# 32pinromtoflash_-_piggyback.net
KiCad netlist of a schematic drawn in EAGLE
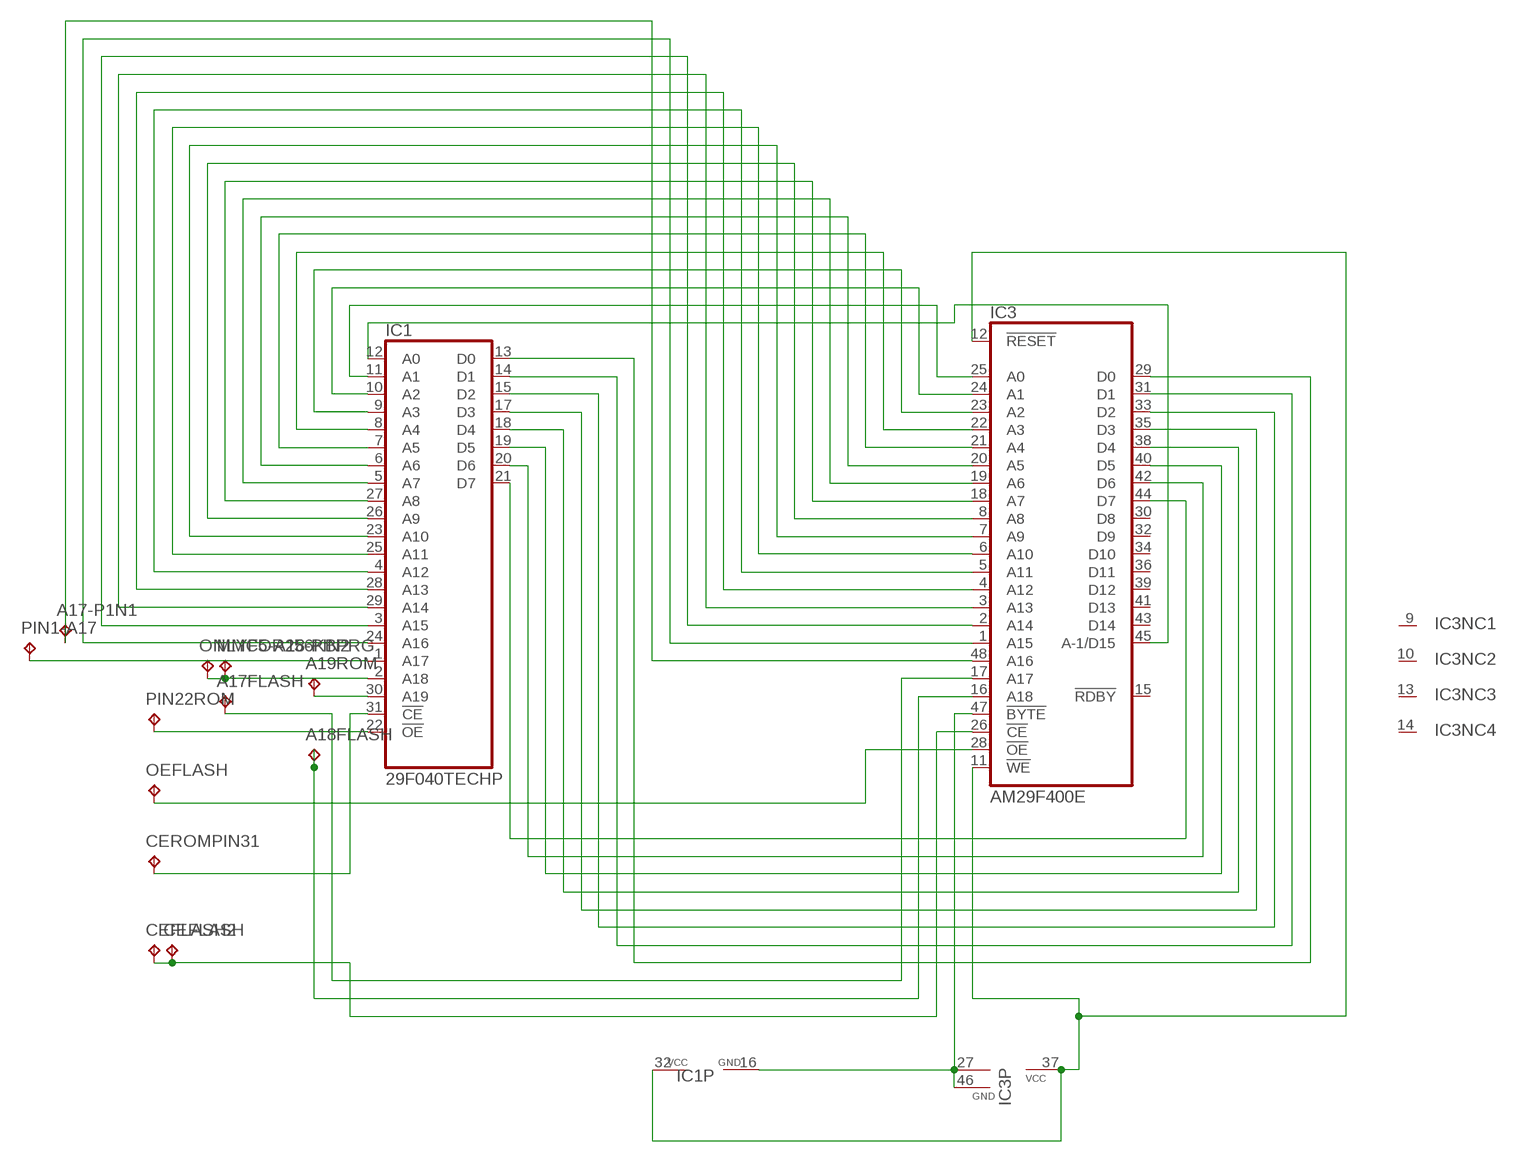
[diagram p0: schematic, sheet 1]

(export (version "E")
  (design (tool "Eeschema 10.0.6"))
  (components
    (comp (ref "A17-P1N1")
      (value "TPTP07SQ")
      (footprint "eagle-import:TP07SQ")
      (libsource (lib "eagle-import") (part "TPTP07SQ"))
    )
    (comp (ref "A17FLASH")
      (value "TPTP07SQ")
      (footprint "eagle-import:TP07SQ")
      (libsource (lib "eagle-import") (part "TPTP07SQ"))
    )
    (comp (ref "A18FLASH")
      (value "TPTP07SQ")
      (footprint "eagle-import:TP07SQ")
      (libsource (lib "eagle-import") (part "TPTP07SQ"))
    )
    (comp (ref "A19ROM")
      (value "TPTP07SQ")
      (footprint "eagle-import:TP07SQ")
      (libsource (lib "eagle-import") (part "TPTP07SQ"))
    )
    (comp (ref "CEFLASH")
      (value "TPTP07SQ")
      (footprint "eagle-import:TP07SQ")
      (libsource (lib "eagle-import") (part "TPTP07SQ"))
    )
    (comp (ref "CEFLASH2")
      (value "TPTP07SQ")
      (footprint "eagle-import:TP07SQ")
      (libsource (lib "eagle-import") (part "TPTP07SQ"))
    )
    (comp (ref "CEROMPIN31")
      (value "TPTP07SQ")
      (footprint "eagle-import:TP07SQ")
      (libsource (lib "eagle-import") (part "TPTP07SQ"))
    )
    (comp (ref "IC1")
      (value "29F040TECHP")
      (footprint "eagle-import:DIL32-3")
      (libsource (lib "eagle-import") (part "29F040PTECH"))
    )
    (comp (ref "IC3")
      (value "AM29F400E")
      (footprint "eagle-import:TSOP48")
      (libsource (lib "eagle-import") (part "AM29F400E"))
    )
    (comp (ref "MMC5-A18-PIN2")
      (value "TPTP07SQ")
      (footprint "eagle-import:TP07SQ")
      (libsource (lib "eagle-import") (part "TPTP07SQ"))
    )
    (comp (ref "OEFLASH")
      (value "TPTP07SQ")
      (footprint "eagle-import:TP07SQ")
      (libsource (lib "eagle-import") (part "TPTP07SQ"))
    )
    (comp (ref "ONLYFOR256KBPRG")
      (value "TPTP07SQ")
      (footprint "eagle-import:TP07SQ")
      (libsource (lib "eagle-import") (part "TPTP07SQ"))
    )
    (comp (ref "PIN1-A17")
      (value "TPTP07SQ")
      (footprint "eagle-import:TP07SQ")
      (libsource (lib "eagle-import") (part "TPTP07SQ"))
    )
    (comp (ref "PIN22ROM")
      (value "TPTP07SQ")
      (footprint "eagle-import:TP07SQ")
      (libsource (lib "eagle-import") (part "TPTP07SQ"))
    )
  )
  (nets
    (net (code "1") (name "Net-(IC1A-A0)") (class "Default")
      (node (ref "IC1") (pin "12") (pinfunction "A0_12") (pintype "input"))
      (node (ref "IC3") (pin "45") (pinfunction "A-1/D15_45") (pintype "tri_state"))
    )
    (net (code "2") (name "Net-(IC1A-A1)") (class "Default")
      (node (ref "IC1") (pin "11") (pinfunction "A1_11") (pintype "input"))
      (node (ref "IC3") (pin "25") (pinfunction "A0_25") (pintype "input"))
    )
    (net (code "3") (name "Net-(IC1A-A2)") (class "Default")
      (node (ref "IC1") (pin "10") (pinfunction "A2_10") (pintype "input"))
      (node (ref "IC3") (pin "24") (pinfunction "A1_24") (pintype "input"))
    )
    (net (code "4") (name "Net-(IC1A-A3)") (class "Default")
      (node (ref "IC1") (pin "9") (pinfunction "A3_9") (pintype "input"))
      (node (ref "IC3") (pin "23") (pinfunction "A2_23") (pintype "input"))
    )
    (net (code "5") (name "Net-(IC1A-A4)") (class "Default")
      (node (ref "IC1") (pin "8") (pinfunction "A4_8") (pintype "input"))
      (node (ref "IC3") (pin "22") (pinfunction "A3_22") (pintype "input"))
    )
    (net (code "6") (name "Net-(IC1A-A5)") (class "Default")
      (node (ref "IC1") (pin "7") (pinfunction "A5_7") (pintype "input"))
      (node (ref "IC3") (pin "21") (pinfunction "A4_21") (pintype "input"))
    )
    (net (code "7") (name "Net-(IC1A-A6)") (class "Default")
      (node (ref "IC1") (pin "6") (pinfunction "A6_6") (pintype "input"))
      (node (ref "IC3") (pin "20") (pinfunction "A5_20") (pintype "input"))
    )
    (net (code "8") (name "Net-(IC1A-A7)") (class "Default")
      (node (ref "IC1") (pin "5") (pinfunction "A7_5") (pintype "input"))
      (node (ref "IC3") (pin "19") (pinfunction "A6_19") (pintype "input"))
    )
    (net (code "9") (name "Net-(IC1A-A8)") (class "Default")
      (node (ref "IC1") (pin "27") (pinfunction "A8_27") (pintype "input"))
      (node (ref "IC3") (pin "18") (pinfunction "A7_18") (pintype "input"))
    )
    (net (code "10") (name "Net-(IC1A-A9)") (class "Default")
      (node (ref "IC1") (pin "26") (pinfunction "A9_26") (pintype "input"))
      (node (ref "IC3") (pin "8") (pinfunction "A8_8") (pintype "input"))
    )
    (net (code "11") (name "Net-(IC1A-A10)") (class "Default")
      (node (ref "IC1") (pin "23") (pinfunction "A10_23") (pintype "input"))
      (node (ref "IC3") (pin "7") (pinfunction "A9_7") (pintype "input"))
    )
    (net (code "12") (name "Net-(IC1A-A11)") (class "Default")
      (node (ref "IC1") (pin "25") (pinfunction "A11_25") (pintype "input"))
      (node (ref "IC3") (pin "6") (pinfunction "A10_6") (pintype "input"))
    )
    (net (code "13") (name "Net-(IC1A-A12)") (class "Default")
      (node (ref "IC1") (pin "4") (pinfunction "A12_4") (pintype "input"))
      (node (ref "IC3") (pin "5") (pinfunction "A11_5") (pintype "input"))
    )
    (net (code "14") (name "Net-(IC1A-A13)") (class "Default")
      (node (ref "IC1") (pin "28") (pinfunction "A13_28") (pintype "input"))
      (node (ref "IC3") (pin "4") (pinfunction "A12_4") (pintype "input"))
    )
    (net (code "15") (name "Net-(IC1A-A14)") (class "Default")
      (node (ref "IC1") (pin "29") (pinfunction "A14_29") (pintype "input"))
      (node (ref "IC3") (pin "3") (pinfunction "A13_3") (pintype "input"))
    )
    (net (code "16") (name "Net-(IC1A-A15)") (class "Default")
      (node (ref "IC1") (pin "3") (pinfunction "A15_3") (pintype "input"))
      (node (ref "IC3") (pin "2") (pinfunction "A14_2") (pintype "input"))
    )
    (net (code "17") (name "Net-(IC1A-A16)") (class "Default")
      (node (ref "IC1") (pin "24") (pinfunction "A16_24") (pintype "input"))
      (node (ref "IC3") (pin "1") (pinfunction "A15_1") (pintype "input"))
    )
    (net (code "18") (name "Net-(IC1A-A17)") (class "Default")
      (node (ref "IC1") (pin "1") (pinfunction "A17_1") (pintype "input"))
      (node (ref "PIN1-A17") (pin "TP") (pinfunction "TP_TP") (pintype "input"))
    )
    (net (code "19") (name "Net-(IC1A-A18)") (class "Default")
      (node (ref "IC1") (pin "2") (pinfunction "A18_2") (pintype "input"))
      (node (ref "MMC5-A18-PIN2") (pin "TP") (pinfunction "TP_TP") (pintype "input"))
      (node (ref "ONLYFOR256KBPRG") (pin "TP") (pinfunction "TP_TP") (pintype "input"))
    )
    (net (code "20") (name "Net-(IC1A-A19)") (class "Default")
      (node (ref "A19ROM") (pin "TP") (pinfunction "TP_TP") (pintype "input"))
      (node (ref "IC1") (pin "30") (pinfunction "A19_30") (pintype "input"))
    )
    (net (code "21") (name "Net-(IC1A-D0)") (class "Default")
      (node (ref "IC1") (pin "13") (pinfunction "D0_13") (pintype "tri_state"))
      (node (ref "IC3") (pin "29") (pinfunction "D0_29") (pintype "tri_state"))
    )
    (net (code "22") (name "Net-(IC1A-D1)") (class "Default")
      (node (ref "IC1") (pin "14") (pinfunction "D1_14") (pintype "tri_state"))
      (node (ref "IC3") (pin "31") (pinfunction "D1_31") (pintype "tri_state"))
    )
    (net (code "23") (name "Net-(IC1A-D2)") (class "Default")
      (node (ref "IC1") (pin "15") (pinfunction "D2_15") (pintype "tri_state"))
      (node (ref "IC3") (pin "33") (pinfunction "D2_33") (pintype "tri_state"))
    )
    (net (code "24") (name "Net-(IC1A-D3)") (class "Default")
      (node (ref "IC1") (pin "17") (pinfunction "D3_17") (pintype "tri_state"))
      (node (ref "IC3") (pin "35") (pinfunction "D3_35") (pintype "tri_state"))
    )
    (net (code "25") (name "Net-(IC1A-D4)") (class "Default")
      (node (ref "IC1") (pin "18") (pinfunction "D4_18") (pintype "tri_state"))
      (node (ref "IC3") (pin "38") (pinfunction "D4_38") (pintype "tri_state"))
    )
    (net (code "26") (name "Net-(IC1A-D5)") (class "Default")
      (node (ref "IC1") (pin "19") (pinfunction "D5_19") (pintype "tri_state"))
      (node (ref "IC3") (pin "40") (pinfunction "D5_40") (pintype "tri_state"))
    )
    (net (code "27") (name "Net-(IC1A-D6)") (class "Default")
      (node (ref "IC1") (pin "20") (pinfunction "D6_20") (pintype "tri_state"))
      (node (ref "IC3") (pin "42") (pinfunction "D6_42") (pintype "tri_state"))
    )
    (net (code "28") (name "Net-(IC1A-D7)") (class "Default")
      (node (ref "IC1") (pin "21") (pinfunction "D7_21") (pintype "input"))
      (node (ref "IC3") (pin "44") (pinfunction "D7_44") (pintype "tri_state"))
    )
    (net (code "29") (name "Net-(IC1A-~{CE})") (class "Default")
      (node (ref "CEROMPIN31") (pin "TP") (pinfunction "TP_TP") (pintype "input"))
      (node (ref "IC1") (pin "31") (pinfunction "~{CE}_31") (pintype "input"))
    )
    (net (code "30") (name "Net-(IC1A-~{OE})") (class "Default")
      (node (ref "IC1") (pin "22") (pinfunction "~{OE}_22") (pintype "input"))
      (node (ref "PIN22ROM") (pin "TP") (pinfunction "TP_TP") (pintype "input"))
    )
    (net (code "31") (name "Net-(IC1B-GND)") (class "Default")
      (node (ref "IC1") (pin "16") (pinfunction "GND_16") (pintype "power_in"))
      (node (ref "IC3") (pin "27") (pinfunction "GND_27") (pintype "power_in"))
      (node (ref "IC3") (pin "46") (pinfunction "GND_46") (pintype "power_in"))
      (node (ref "IC3") (pin "47") (pinfunction "~{BYTE}_47") (pintype "input"))
    )
    (net (code "32") (name "Net-(IC1B-VCC)") (class "Default")
      (node (ref "IC1") (pin "32") (pinfunction "VCC_32") (pintype "power_in"))
      (node (ref "IC3") (pin "11") (pinfunction "~{WE}_11") (pintype "input"))
      (node (ref "IC3") (pin "12") (pinfunction "~{RESET}_12") (pintype "input"))
      (node (ref "IC3") (pin "37") (pinfunction "VCC_37") (pintype "power_in"))
    )
    (net (code "33") (name "Net-(IC3A-A16)") (class "Default")
      (node (ref "A17-P1N1") (pin "TP") (pinfunction "TP_TP") (pintype "input"))
      (node (ref "IC3") (pin "48") (pinfunction "A16_48") (pintype "input"))
    )
    (net (code "34") (name "Net-(IC3A-A17)") (class "Default")
      (node (ref "A17FLASH") (pin "TP") (pinfunction "TP_TP") (pintype "input"))
      (node (ref "IC3") (pin "17") (pinfunction "A17_17") (pintype "input"))
    )
    (net (code "35") (name "Net-(IC3A-A18)") (class "Default")
      (node (ref "A18FLASH") (pin "TP") (pinfunction "TP_TP") (pintype "input"))
      (node (ref "IC3") (pin "16") (pinfunction "A18_16") (pintype "input"))
    )
    (net (code "36") (name "Net-(IC3A-~{CE})") (class "Default")
      (node (ref "CEFLASH") (pin "TP") (pinfunction "TP_TP") (pintype "input"))
      (node (ref "CEFLASH2") (pin "TP") (pinfunction "TP_TP") (pintype "input"))
      (node (ref "IC3") (pin "26") (pinfunction "~{CE}_26") (pintype "input"))
    )
    (net (code "37") (name "Net-(IC3A-~{OE})") (class "Default")
      (node (ref "IC3") (pin "28") (pinfunction "~{OE}_28") (pintype "input"))
      (node (ref "OEFLASH") (pin "TP") (pinfunction "TP_TP") (pintype "input"))
    )
    (net (code "38") (name "unconnected-(IC3A-D8-Pad30)") (class "Default")
      (node (ref "IC3") (pin "30") (pinfunction "D8_30") (pintype "tri_state"))
    )
    (net (code "39") (name "unconnected-(IC3A-D9-Pad32)") (class "Default")
      (node (ref "IC3") (pin "32") (pinfunction "D9_32") (pintype "tri_state"))
    )
    (net (code "40") (name "unconnected-(IC3A-D10-Pad34)") (class "Default")
      (node (ref "IC3") (pin "34") (pinfunction "D10_34") (pintype "tri_state"))
    )
    (net (code "41") (name "unconnected-(IC3A-D11-Pad36)") (class "Default")
      (node (ref "IC3") (pin "36") (pinfunction "D11_36") (pintype "tri_state"))
    )
    (net (code "42") (name "unconnected-(IC3A-D12-Pad39)") (class "Default")
      (node (ref "IC3") (pin "39") (pinfunction "D12_39") (pintype "tri_state"))
    )
    (net (code "43") (name "unconnected-(IC3A-D13-Pad41)") (class "Default")
      (node (ref "IC3") (pin "41") (pinfunction "D13_41") (pintype "tri_state"))
    )
    (net (code "44") (name "unconnected-(IC3A-D14-Pad43)") (class "Default")
      (node (ref "IC3") (pin "43") (pinfunction "D14_43") (pintype "tri_state"))
    )
    (net (code "45") (name "unconnected-(IC3A-~{RDBY}-Pad15)") (class "Default")
      (node (ref "IC3") (pin "15") (pinfunction "~{RDBY}_15") (pintype "output"))
    )
    (net (code "46") (name "unconnected-(IC3B-NC-Pad9)") (class "Default")
      (node (ref "IC3") (pin "9") (pinfunction "NC_9") (pintype "no_connect"))
    )
    (net (code "47") (name "unconnected-(IC3C-NC-Pad10)") (class "Default")
      (node (ref "IC3") (pin "10") (pinfunction "NC_10") (pintype "no_connect"))
    )
    (net (code "48") (name "unconnected-(IC3D-NC-Pad13)") (class "Default")
      (node (ref "IC3") (pin "13") (pinfunction "NC_13") (pintype "no_connect"))
    )
    (net (code "49") (name "unconnected-(IC3E-NC-Pad14)") (class "Default")
      (node (ref "IC3") (pin "14") (pinfunction "NC_14") (pintype "no_connect"))
    )
  )
)
